# CR76D.net
KiCad netlist of a schematic drawn in EAGLE
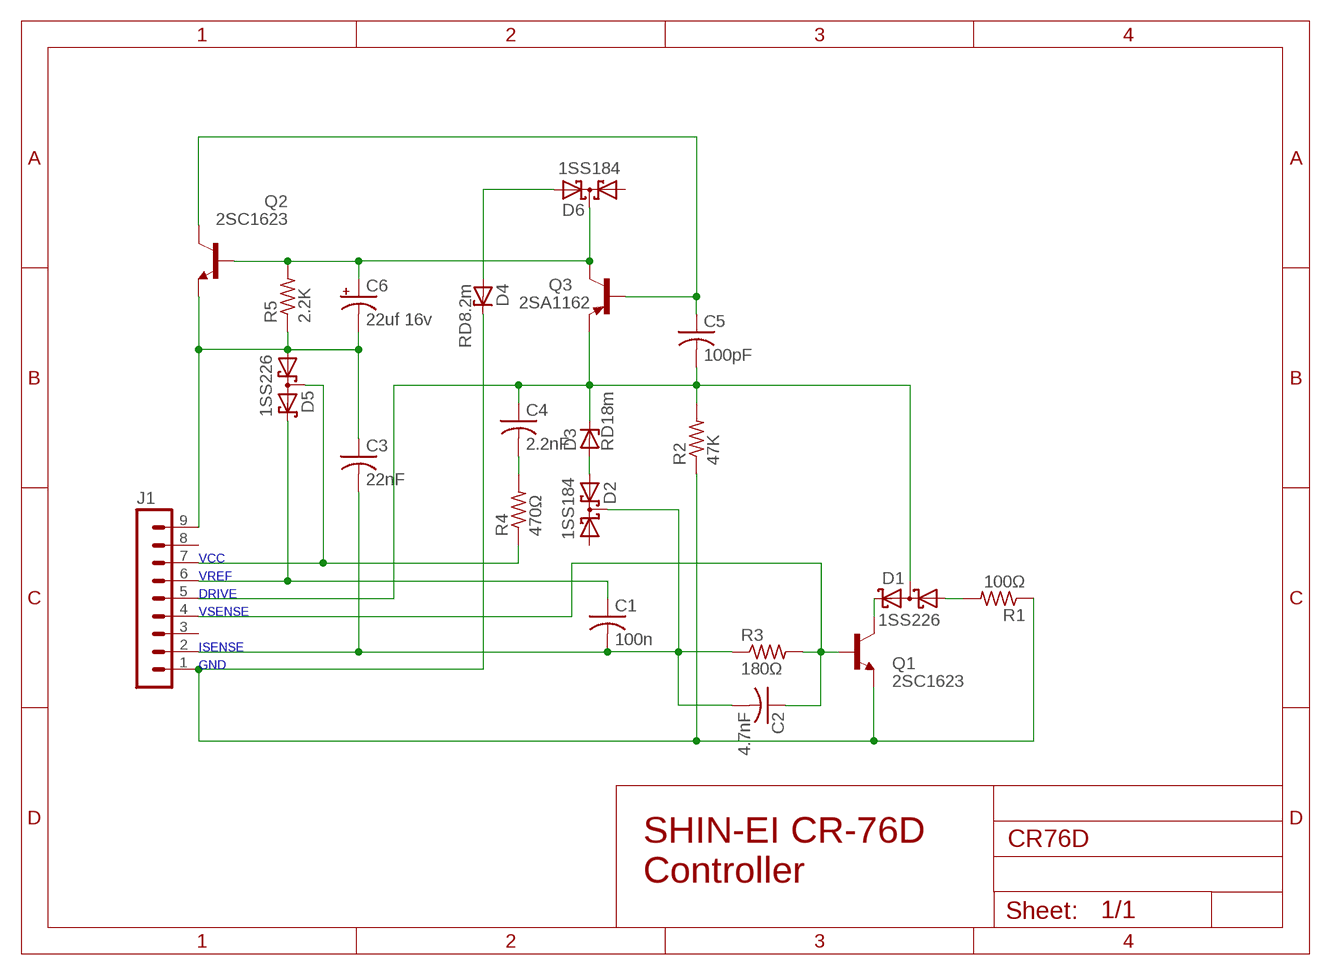
[diagram p0: schematic, sheet 1]

(export (version "E")
  (design (tool "Eeschema 10.0.6"))
  (components
    (comp (ref "C1")
      (value "100n")
      (footprint "eagle-import:C1206")
      (libsource (lib "eagle-import") (part "C-USC1206"))
    )
    (comp (ref "C2")
      (value "4.7nF")
      (footprint "eagle-import:C0805")
      (libsource (lib "eagle-import") (part "resistor_C-USC0805"))
    )
    (comp (ref "C3")
      (value "22nF")
      (footprint "eagle-import:C0805")
      (libsource (lib "eagle-import") (part "resistor_C-USC0805"))
    )
    (comp (ref "C4")
      (value "2.2nF")
      (footprint "eagle-import:C0805")
      (libsource (lib "eagle-import") (part "resistor_C-USC0805"))
    )
    (comp (ref "C5")
      (value "100pF")
      (footprint "eagle-import:C0805")
      (libsource (lib "eagle-import") (part "resistor_C-USC0805"))
    )
    (comp (ref "C6")
      (value "22uf 16v")
      (footprint "eagle-import:B_3528-21W")
      (libsource (lib "eagle-import") (part "CPOL-USB/3528-21W"))
    )
    (comp (ref "D1")
      (value "1SS226")
      (footprint "eagle-import:SOT23")
      (libsource (lib "eagle-import") (part "BAS40-04"))
    )
    (comp (ref "D2")
      (value "1SS184")
      (footprint "eagle-import:SOT23")
      (libsource (lib "eagle-import") (part "BAS40-05"))
    )
    (comp (ref "D3")
      (value "RD18m")
      (footprint "eagle-import:SOT23")
      (libsource (lib "eagle-import") (part "ZENER-DIODESOT23"))
    )
    (comp (ref "D4")
      (value "RD8.2m")
      (footprint "eagle-import:SOT23")
      (libsource (lib "eagle-import") (part "ZENER-DIODESOT23"))
    )
    (comp (ref "D5")
      (value "1SS226")
      (footprint "eagle-import:SOT23")
      (libsource (lib "eagle-import") (part "BAS40-04"))
    )
    (comp (ref "D6")
      (value "1SS184")
      (footprint "eagle-import:SOT23")
      (libsource (lib "eagle-import") (part "BAS40-05"))
    )
    (comp (ref "J1")
      (value "MA09-1")
      (footprint "eagle-import:MA09-1")
      (libsource (lib "eagle-import") (part "MA09-1"))
    )
    (comp (ref "Q1")
      (value "2SC1623")
      (footprint "eagle-import:SOT23-BEC")
      (libsource (lib "eagle-import") (part "BC849SMD"))
    )
    (comp (ref "Q2")
      (value "2SC1623")
      (footprint "eagle-import:SOT23-BEC")
      (libsource (lib "eagle-import") (part "BC849SMD"))
    )
    (comp (ref "Q3")
      (value "2SA1162")
      (footprint "eagle-import:SOT23")
      (libsource (lib "eagle-import") (part "BCX71SMD"))
    )
    (comp (ref "R1")
      (value "100Ω")
      (footprint "eagle-import:R0805W")
      (libsource (lib "eagle-import") (part "R-US_R0805W"))
    )
    (comp (ref "R2")
      (value "47K")
      (footprint "eagle-import:R0805W")
      (libsource (lib "eagle-import") (part "R-US_R0805W"))
    )
    (comp (ref "R3")
      (value "180Ω")
      (footprint "eagle-import:R0805W")
      (libsource (lib "eagle-import") (part "R-US_R0805W"))
    )
    (comp (ref "R4")
      (value "470Ω")
      (footprint "eagle-import:R0805W")
      (libsource (lib "eagle-import") (part "R-US_R0805W"))
    )
    (comp (ref "R5")
      (value "2.2K")
      (footprint "eagle-import:R0805W")
      (libsource (lib "eagle-import") (part "R-US_R0805W"))
    )
  )
  (nets
    (net (code "1") (name "/DRIVE") (class "Default")
      (node (ref "C4") (pin "1") (pinfunction "1_1") (pintype "passive"))
      (node (ref "C5") (pin "2") (pinfunction "2_2") (pintype "passive"))
      (node (ref "D1") (pin "3") (pinfunction "C1A2_3") (pintype "passive"))
      (node (ref "D3") (pin "3") (pinfunction "C_3") (pintype "passive"))
      (node (ref "J1") (pin "5") (pinfunction "5_5") (pintype "passive"))
      (node (ref "Q3") (pin "2") (pinfunction "E_2") (pintype "passive"))
      (node (ref "R2") (pin "2") (pinfunction "2_2") (pintype "passive"))
    )
    (net (code "2") (name "/GND") (class "Default")
      (node (ref "D4") (pin "3") (pinfunction "C_3") (pintype "passive"))
      (node (ref "J1") (pin "1") (pinfunction "1_1") (pintype "passive"))
      (node (ref "Q1") (pin "E") (pinfunction "E_E") (pintype "passive"))
      (node (ref "R1") (pin "1") (pinfunction "1_1") (pintype "passive"))
      (node (ref "R2") (pin "1") (pinfunction "1_1") (pintype "passive"))
    )
    (net (code "3") (name "/ISENSE") (class "Default")
      (node (ref "C1") (pin "2") (pinfunction "2_2") (pintype "passive"))
      (node (ref "C2") (pin "2") (pinfunction "2_2") (pintype "passive"))
      (node (ref "C3") (pin "2") (pinfunction "2_2") (pintype "passive"))
      (node (ref "D2") (pin "3") (pinfunction "C_3") (pintype "passive"))
      (node (ref "J1") (pin "2") (pinfunction "2_2") (pintype "passive"))
      (node (ref "R3") (pin "1") (pinfunction "1_1") (pintype "passive"))
    )
    (net (code "4") (name "/VCC") (class "Default")
      (node (ref "D5") (pin "3") (pinfunction "C1A2_3") (pintype "passive"))
      (node (ref "J1") (pin "7") (pinfunction "7_7") (pintype "passive"))
      (node (ref "R4") (pin "1") (pinfunction "1_1") (pintype "passive"))
    )
    (net (code "5") (name "/VREF") (class "Default")
      (node (ref "C1") (pin "1") (pinfunction "1_1") (pintype "passive"))
      (node (ref "D5") (pin "2") (pinfunction "C2_2") (pintype "passive"))
      (node (ref "J1") (pin "6") (pinfunction "6_6") (pintype "passive"))
    )
    (net (code "6") (name "/VSENSE") (class "Default")
      (node (ref "C2") (pin "1") (pinfunction "1_1") (pintype "passive"))
      (node (ref "J1") (pin "4") (pinfunction "4_4") (pintype "passive"))
      (node (ref "Q1") (pin "B") (pinfunction "B_B") (pintype "passive"))
      (node (ref "R3") (pin "2") (pinfunction "2_2") (pintype "passive"))
    )
    (net (code "7") (name "Net-(C4-Pad2)") (class "Default")
      (node (ref "C4") (pin "2") (pinfunction "2_2") (pintype "passive"))
      (node (ref "R4") (pin "2") (pinfunction "2_2") (pintype "passive"))
    )
    (net (code "8") (name "Net-(D1-A1)") (class "Default")
      (node (ref "D1") (pin "1") (pinfunction "A1_1") (pintype "passive"))
      (node (ref "R1") (pin "2") (pinfunction "2_2") (pintype "passive"))
    )
    (net (code "9") (name "Net-(D1-C2)") (class "Default")
      (node (ref "D1") (pin "2") (pinfunction "C2_2") (pintype "passive"))
      (node (ref "Q1") (pin "C") (pinfunction "C_C") (pintype "passive"))
    )
    (net (code "10") (name "Net-(D2-A2)") (class "Default")
      (node (ref "D2") (pin "2") (pinfunction "A2_2") (pintype "passive"))
      (node (ref "D3") (pin "1") (pinfunction "A_1") (pintype "passive"))
    )
    (net (code "11") (name "Net-(D4-A)") (class "Default")
      (node (ref "D4") (pin "1") (pinfunction "A_1") (pintype "passive"))
      (node (ref "D6") (pin "2") (pinfunction "A2_2") (pintype "passive"))
    )
    (net (code "12") (name "Net-(D5-A1)") (class "Default")
      (node (ref "C3") (pin "1") (pinfunction "1_1") (pintype "passive"))
      (node (ref "C6") (pin "-") (pinfunction "-_-") (pintype "passive"))
      (node (ref "D5") (pin "1") (pinfunction "A1_1") (pintype "passive"))
      (node (ref "J1") (pin "9") (pinfunction "9_9") (pintype "passive"))
      (node (ref "Q2") (pin "E") (pinfunction "E_E") (pintype "passive"))
      (node (ref "R5") (pin "1") (pinfunction "1_1") (pintype "passive"))
    )
    (net (code "13") (name "Net-(D6-C)") (class "Default")
      (node (ref "C6") (pin "+") (pinfunction "+_+") (pintype "passive"))
      (node (ref "D6") (pin "3") (pinfunction "C_3") (pintype "passive"))
      (node (ref "Q2") (pin "B") (pinfunction "B_B") (pintype "passive"))
      (node (ref "Q3") (pin "3") (pinfunction "C_3") (pintype "passive"))
      (node (ref "R5") (pin "2") (pinfunction "2_2") (pintype "passive"))
    )
    (net (code "14") (name "Net-(Q3-B)") (class "Default")
      (node (ref "C5") (pin "1") (pinfunction "1_1") (pintype "passive"))
      (node (ref "Q2") (pin "C") (pinfunction "C_C") (pintype "passive"))
      (node (ref "Q3") (pin "1") (pinfunction "B_1") (pintype "passive"))
    )
    (net (code "15") (name "unconnected-(D2-A1-Pad1)") (class "Default")
      (node (ref "D2") (pin "1") (pinfunction "A1_1") (pintype "passive"))
    )
    (net (code "16") (name "unconnected-(D6-A1-Pad1)") (class "Default")
      (node (ref "D6") (pin "1") (pinfunction "A1_1") (pintype "passive"))
    )
    (net (code "17") (name "unconnected-(J1-Pad3)") (class "Default")
      (node (ref "J1") (pin "3") (pinfunction "3_3") (pintype "passive"))
    )
    (net (code "18") (name "unconnected-(J1-Pad8)") (class "Default")
      (node (ref "J1") (pin "8") (pinfunction "8_8") (pintype "passive"))
    )
  )
)
